# OneKey_Download.net
KiCad netlist of a schematic drawn in Altium Designer
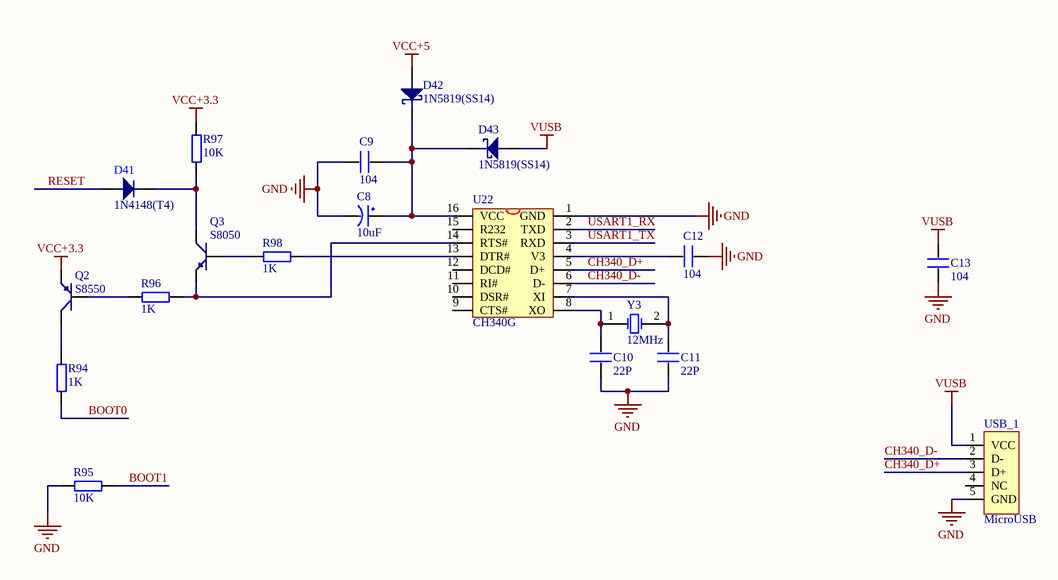
[diagram p0: OneKey_Download.SchDoc]

(export (version "E")
  (design (tool "Eeschema 10.0.6"))
  (components
    (comp (ref "C8") (value "10uF") (footprint "CAP2.54") (libsource (lib "mylib") (part "CAP")))
    (comp (ref "C9") (value "104") (footprint "0805-CAP") (libsource (lib "mylib") (part "C")))
    (comp (ref "C10") (value "22P") (footprint "0805-CAP") (libsource (lib "mylib") (part "C")))
    (comp (ref "C11") (value "22P") (footprint "0805-CAP") (libsource (lib "mylib") (part "C")))
    (comp (ref "C12") (value "104") (footprint "0805-CAP") (libsource (lib "mylib") (part "C")))
    (comp (ref "C13") (value "104") (footprint "0805-CAP") (libsource (lib "mylib") (part "C")))
    (comp (ref "D41")
      (value "1N4148(T4)")
      (footprint "SOD-123")
      (description "高速开关二极管")
      (libsource (lib "mylib") (part "1N4148"))
    )
    (comp (ref "D42")
      (value "1N5819(SS14)")
      (footprint "DO-214AC(SMA)")
      (description "肖特基二极管")
      (libsource (lib "mylib") (part "1N5819(SS14)"))
    )
    (comp (ref "D43")
      (value "1N5819(SS14)")
      (footprint "DO-214AC(SMA)")
      (description "肖特基二极管")
      (libsource (lib "mylib") (part "1N5819(SS14)"))
    )
    (comp (ref "Q2")
      (value "S8550")
      (footprint "SOT-23R")
      (description "8550/BCW68")
      (libsource (lib "mylib") (part "PNP"))
    )
    (comp (ref "Q3")
      (value "S8050")
      (footprint "SOT-23R")
      (description "8050/BCW846/BCW847")
      (libsource (lib "mylib") (part "NPN"))
    )
    (comp (ref "R94") (value "1K") (footprint "0805-RES") (libsource (lib "mylib") (part "Res")))
    (comp (ref "R95") (value "10K") (footprint "0805-RES") (libsource (lib "mylib") (part "Res")))
    (comp (ref "R96") (value "1K") (footprint "0805-RES") (libsource (lib "mylib") (part "Res")))
    (comp (ref "R97") (value "10K") (footprint "0805-RES") (libsource (lib "mylib") (part "Res")))
    (comp (ref "R98") (value "1K") (footprint "0805-RES") (libsource (lib "mylib") (part "Res")))
    (comp (ref "U22")
      (value "CH340G")
      (footprint "SOP16M")
      (description "USB2UART")
      (libsource (lib "mylib") (part "CH340G"))
    )
    (comp (ref "USB_1") (value "MicroUSB") (footprint "USB_micro") (libsource (lib "mylib") (part "USB5")))
    (comp (ref "Y3")
      (value "12MHz")
      (footprint "XTAL_US")
      (description "Crystal Oscillator")
      (fields (field (name "PUBLISHER") "Altium Limited"))
      (libsource (lib "mylib") (part "XTAL"))
    )
  )
  (nets
    (net (code "1") (name "/BOOT0") (class "Default") (node (ref "R94") (pin "1") (pintype "passive")))
    (net (code "2") (name "/BOOT1") (class "Default") (node (ref "R95") (pin "2") (pintype "passive")))
    (net (code "3") (name "/CH340_D+") (class "Default")
      (node (ref "U22") (pin "5") (pinfunction "D+_5") (pintype "passive"))
      (node (ref "USB_1") (pin "3") (pinfunction "D+_3") (pintype "passive"))
    )
    (net (code "4") (name "/CH340_D-") (class "Default")
      (node (ref "U22") (pin "6") (pinfunction "D-_6") (pintype "passive"))
      (node (ref "USB_1") (pin "2") (pinfunction "D-_2") (pintype "passive"))
    )
    (net (code "5") (name "/RESET") (class "Default") (node (ref "D41") (pin "1") (pintype "passive")))
    (net (code "6") (name "/USART1_RX") (class "Default")
      (node (ref "U22") (pin "2") (pinfunction "TXD_2") (pintype "passive"))
    )
    (net (code "7") (name "/USART1_TX") (class "Default")
      (node (ref "U22") (pin "3") (pinfunction "RXD_3") (pintype "passive"))
    )
    (net (code "8") (name "GND") (class "Default")
      (node (ref "C10") (pin "1") (pintype "passive"))
      (node (ref "C11") (pin "1") (pintype "passive"))
      (node (ref "C12") (pin "2") (pintype "passive"))
      (node (ref "C13") (pin "1") (pintype "passive"))
      (node (ref "C8") (pin "2") (pinfunction "GND_2") (pintype "passive"))
      (node (ref "C9") (pin "1") (pintype "passive"))
      (node (ref "R95") (pin "1") (pintype "passive"))
      (node (ref "U22") (pin "1") (pinfunction "GND_1") (pintype "passive"))
      (node (ref "USB_1") (pin "5") (pinfunction "GND_5") (pintype "passive"))
    )
    (net (code "9") (name "Net-(C8-VCC)") (class "Default")
      (node (ref "C8") (pin "1") (pinfunction "VCC_1") (pintype "passive"))
      (node (ref "C9") (pin "2") (pintype "passive"))
      (node (ref "D42") (pin "2") (pintype "passive"))
      (node (ref "D43") (pin "2") (pintype "passive"))
      (node (ref "U22") (pin "16") (pinfunction "VCC_16") (pintype "passive"))
    )
    (net (code "10") (name "Net-(Q2-B)") (class "Default")
      (node (ref "Q2") (pin "2") (pinfunction "B_2") (pintype "passive"))
      (node (ref "R96") (pin "1") (pintype "passive"))
    )
    (net (code "11") (name "Net-(Q2-C)") (class "Default")
      (node (ref "Q2") (pin "3") (pinfunction "C_3") (pintype "passive"))
      (node (ref "R94") (pin "2") (pintype "passive"))
    )
    (net (code "12") (name "Net-(Q3-B)") (class "Default")
      (node (ref "Q3") (pin "2") (pinfunction "B_2") (pintype "passive"))
      (node (ref "R98") (pin "1") (pintype "passive"))
    )
    (net (code "13") (name "Net-(Q3-C)") (class "Default")
      (node (ref "D41") (pin "2") (pintype "passive"))
      (node (ref "Q3") (pin "3") (pinfunction "C_3") (pintype "passive"))
      (node (ref "R97") (pin "1") (pintype "passive"))
    )
    (net (code "14") (name "Net-(Q3-E)") (class "Default")
      (node (ref "Q3") (pin "1") (pinfunction "E_1") (pintype "passive"))
      (node (ref "R96") (pin "2") (pintype "passive"))
      (node (ref "U22") (pin "14") (pinfunction "RTS#_14") (pintype "passive"))
    )
    (net (code "15") (name "Net-(U22-DTR#)") (class "Default")
      (node (ref "R98") (pin "2") (pintype "passive"))
      (node (ref "U22") (pin "13") (pinfunction "DTR#_13") (pintype "passive"))
    )
    (net (code "16") (name "Net-(U22-V3)") (class "Default")
      (node (ref "C12") (pin "1") (pintype "passive"))
      (node (ref "U22") (pin "4") (pinfunction "V3_4") (pintype "passive"))
    )
    (net (code "17") (name "Net-(U22-XI)") (class "Default")
      (node (ref "C11") (pin "2") (pintype "passive"))
      (node (ref "U22") (pin "7") (pinfunction "XI_7") (pintype "passive"))
      (node (ref "Y3") (pin "2") (pinfunction "OSC2_2") (pintype "passive"))
    )
    (net (code "18") (name "Net-(U22-XO)") (class "Default")
      (node (ref "C10") (pin "2") (pintype "passive"))
      (node (ref "U22") (pin "8") (pinfunction "XO_8") (pintype "passive"))
      (node (ref "Y3") (pin "1") (pinfunction "OSC1_1") (pintype "passive"))
    )
    (net (code "19") (name "VCC+3.3") (class "Default")
      (node (ref "Q2") (pin "1") (pinfunction "E_1") (pintype "passive"))
      (node (ref "R97") (pin "2") (pintype "passive"))
    )
    (net (code "20") (name "VCC+5") (class "Default") (node (ref "D42") (pin "1") (pintype "passive")))
    (net (code "21") (name "VUSB") (class "Default")
      (node (ref "C13") (pin "2") (pintype "passive"))
      (node (ref "D43") (pin "1") (pintype "passive"))
      (node (ref "USB_1") (pin "1") (pinfunction "VCC_1") (pintype "passive"))
    )
    (net (code "22") (name "unconnected-(U22-CTS#-Pad9)") (class "Default")
      (node (ref "U22") (pin "9") (pinfunction "CTS#_9") (pintype "passive"))
    )
    (net (code "23") (name "unconnected-(U22-DCD#-Pad12)") (class "Default")
      (node (ref "U22") (pin "12") (pinfunction "DCD#_12") (pintype "passive"))
    )
    (net (code "24") (name "unconnected-(U22-DSR#-Pad10)") (class "Default")
      (node (ref "U22") (pin "10") (pinfunction "DSR#_10") (pintype "passive"))
    )
    (net (code "25") (name "unconnected-(U22-R232-Pad15)") (class "Default")
      (node (ref "U22") (pin "15") (pinfunction "R232_15") (pintype "passive"))
    )
    (net (code "26") (name "unconnected-(U22-RI#-Pad11)") (class "Default")
      (node (ref "U22") (pin "11") (pinfunction "RI#_11") (pintype "passive"))
    )
    (net (code "27") (name "unconnected-(USB_1-NC-Pad4)") (class "Default")
      (node (ref "USB_1") (pin "4") (pinfunction "NC_4") (pintype "passive"))
    )
  )
)
